# Sheet1.net
KiCad netlist of a schematic drawn in Altium Designer
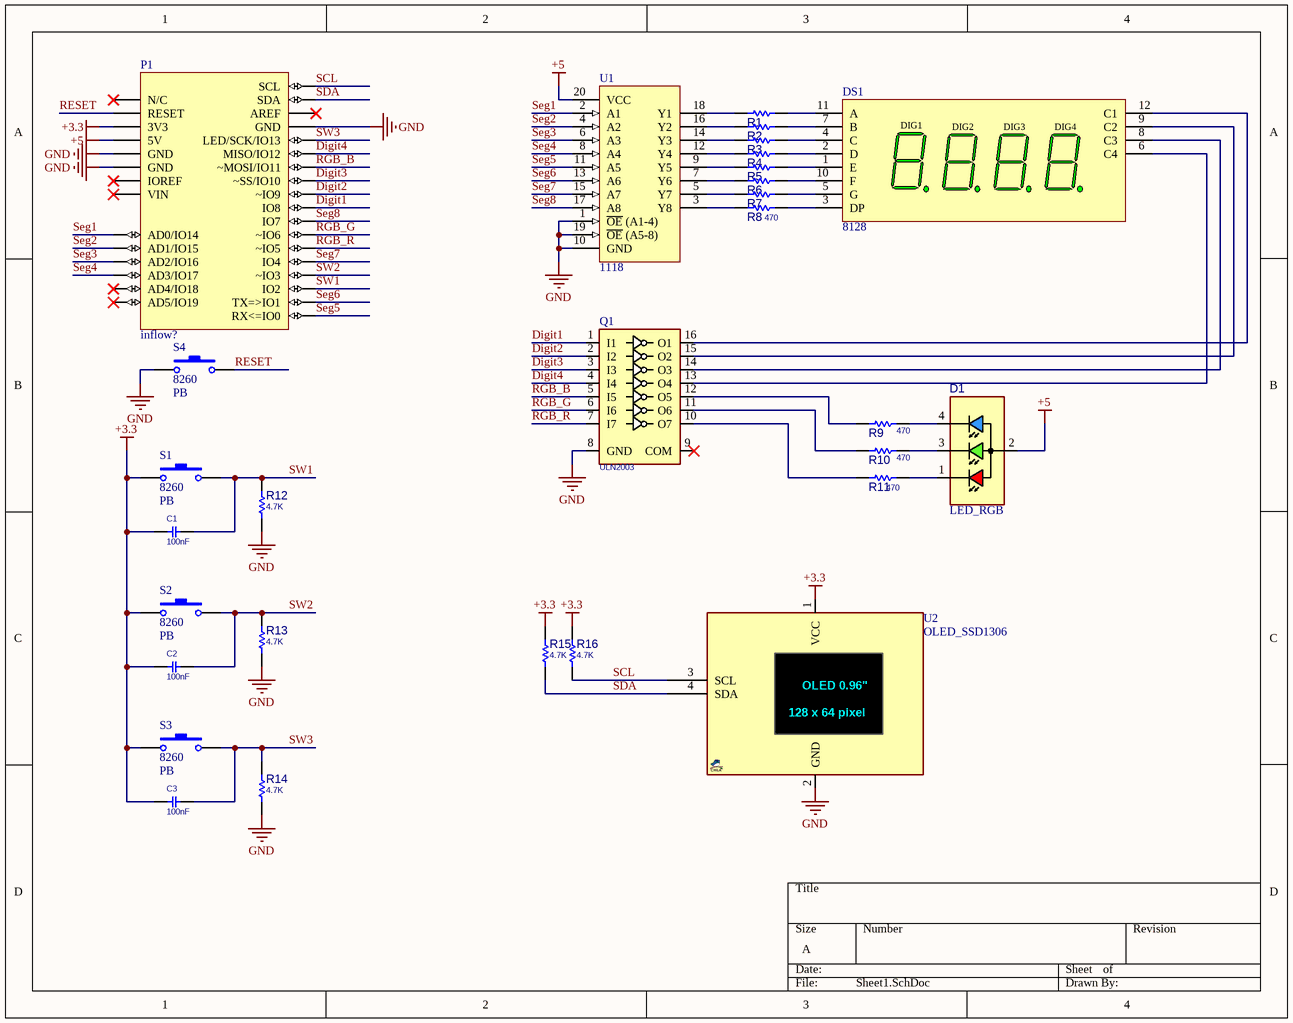
[diagram p0: Sheet1.SchDoc]

(export (version "E")
  (design (tool "Eeschema 10.0.6"))
  (components
    (comp (ref "C1")
      (value "100nF")
      (footprint "C_CER_D3")
      (description "CAP, THD, CER MULTI LAYER,")
      (fields (field (name "MANF_P#") "MANF_PART#") (field (name "MANF") "MANF"))
      (libsource (lib "Chila_PCB") (part "CAP_THD_CERML"))
    )
    (comp (ref "C2")
      (value "100nF")
      (footprint "C_CER_D3")
      (description "CAP, THD, CER MULTI LAYER,")
      (fields (field (name "MANF_P#") "MANF_PART#") (field (name "MANF") "MANF"))
      (libsource (lib "Chila_PCB") (part "CAP_THD_CERML"))
    )
    (comp (ref "C3")
      (value "100nF")
      (footprint "C_CER_D3")
      (description "CAP, THD, CER MULTI LAYER,")
      (fields (field (name "MANF_P#") "MANF_PART#") (field (name "MANF") "MANF"))
      (libsource (lib "Chila_PCB") (part "CAP_THD_CERML"))
    )
    (comp (ref "D1")
      (value "LED_RGB")
      (footprint "LED5RGB")
      (description "LED, THD, 5MM, RGB COMMON CATHODE")
      (fields (field (name "MANF_P#") "YSL-R596CR3G4B5C-C10") (field (name "MANF") "CHINA YOUNG"))
      (libsource (lib "Chila_PCB") (part "LED_THD_5MM_RGB_CA"))
    )
    (comp (ref "DS1")
      (value "4Digit, Red")
      (footprint "7Seg-MPX4-30.2x14.1mm")
      (description "7Segment-MPX4-CC")
      (fields (field (name "INFLOW") "8128"))
      (libsource (lib "aKaReZa") (part "ModSen_7Seg_MPX4_CC"))
    )
    (comp (ref "P1")
      (value "UNO")
      (footprint "Arduino_uno_S_3")
      (description "Arduino uno slave")
      (fields (field (name "INFLOW") "inflow?"))
      (libsource (lib "aKaReZa") (part "Con_Arduino_UNO_S"))
    )
    (comp (ref "Q1")
      (value "ULN2003")
      (footprint "DIP_16")
      (description "Darlington, 7-CH, 50V, 0.5A")
      (fields (field (name "MANF_P#") "ULN2003A") (field (name "MANF") "DIODES"))
      (libsource (lib "Chila_PCB") (part "ULN2003_DIP16"))
    )
    (comp (ref "R1")
      (value "470")
      (footprint "R1206")
      (description "RESISTOR, SMD")
      (libsource (lib "Chila_PCB") (part "RES_SMD_1206"))
    )
    (comp (ref "R2")
      (value "470")
      (footprint "R1206")
      (description "RESISTOR, SMD")
      (libsource (lib "Chila_PCB") (part "RES_SMD_1206"))
    )
    (comp (ref "R3")
      (value "470")
      (footprint "R1206")
      (description "RESISTOR, SMD")
      (libsource (lib "Chila_PCB") (part "RES_SMD_1206"))
    )
    (comp (ref "R4")
      (value "470")
      (footprint "R1206")
      (description "RESISTOR, SMD")
      (libsource (lib "Chila_PCB") (part "RES_SMD_1206"))
    )
    (comp (ref "R5")
      (value "470")
      (footprint "R1206")
      (description "RESISTOR, SMD")
      (libsource (lib "Chila_PCB") (part "RES_SMD_1206"))
    )
    (comp (ref "R6")
      (value "470")
      (footprint "R1206")
      (description "RESISTOR, SMD")
      (libsource (lib "Chila_PCB") (part "RES_SMD_1206"))
    )
    (comp (ref "R7")
      (value "470")
      (footprint "R1206")
      (description "RESISTOR, SMD")
      (libsource (lib "Chila_PCB") (part "RES_SMD_1206"))
    )
    (comp (ref "R8")
      (value "470")
      (footprint "R1206")
      (description "RESISTOR, SMD")
      (libsource (lib "Chila_PCB") (part "RES_SMD_1206"))
    )
    (comp (ref "R9")
      (value "470")
      (footprint "R1206")
      (description "RESISTOR, SMD")
      (libsource (lib "Chila_PCB") (part "RES_SMD_1206"))
    )
    (comp (ref "R10")
      (value "470")
      (footprint "R1206")
      (description "RESISTOR, SMD")
      (libsource (lib "Chila_PCB") (part "RES_SMD_1206"))
    )
    (comp (ref "R11")
      (value "470")
      (footprint "R1206")
      (description "RESISTOR, SMD")
      (libsource (lib "Chila_PCB") (part "RES_SMD_1206"))
    )
    (comp (ref "R12")
      (value "4.7K")
      (footprint "R1206")
      (description "RESISTOR, SMD")
      (libsource (lib "Chila_PCB") (part "RES_SMD_1206"))
    )
    (comp (ref "R13")
      (value "4.7K")
      (footprint "R1206")
      (description "RESISTOR, SMD")
      (libsource (lib "Chila_PCB") (part "RES_SMD_1206"))
    )
    (comp (ref "R14")
      (value "4.7K")
      (footprint "R1206")
      (description "RESISTOR, SMD")
      (libsource (lib "Chila_PCB") (part "RES_SMD_1206"))
    )
    (comp (ref "R15")
      (value "4.7K")
      (footprint "R1206")
      (description "RESISTOR, SMD")
      (libsource (lib "Chila_PCB") (part "RES_SMD_1206"))
    )
    (comp (ref "R16")
      (value "4.7K")
      (footprint "R1206")
      (description "RESISTOR, SMD")
      (libsource (lib "Chila_PCB") (part "RES_SMD_1206"))
    )
    (comp (ref "S1")
      (value "PB")
      (footprint "SW_PB_SMD_2PIN_SPST_6X3X2")
      (description "SMT Tactile ‎Switch")
      (fields (field (name "INFLOW") "8260"))
      (libsource (lib "aKaReZa") (part "SW_PushButton_2_SMD"))
    )
    (comp (ref "S2")
      (value "PB")
      (footprint "SW_PB_SMD_2PIN_SPST_6X3X2")
      (description "SMT Tactile ‎Switch")
      (fields (field (name "INFLOW") "8260"))
      (libsource (lib "aKaReZa") (part "SW_PushButton_2_SMD"))
    )
    (comp (ref "S3")
      (value "PB")
      (footprint "SW_PB_SMD_2PIN_SPST_6X3X2")
      (description "SMT Tactile ‎Switch")
      (fields (field (name "INFLOW") "8260"))
      (libsource (lib "aKaReZa") (part "SW_PushButton_2_SMD"))
    )
    (comp (ref "S4")
      (value "PB")
      (footprint "SW_PB_SMD_2PIN_SPST_6X3X2")
      (description "SMT Tactile ‎Switch")
      (fields (field (name "INFLOW") "8260"))
      (libsource (lib "aKaReZa") (part "SW_PushButton_2_SMD"))
    )
    (comp (ref "U1")
      (value "74HCT244")
      (footprint "PDIP20")
      (description "Octal Bus Buffer with 3 State Outputs (Non Inverted)")
      (fields (field (name "INFLOW") "1118"))
      (libsource (lib "aKaReZa") (part "IC_Logic_74HCT244"))
    )
    (comp (ref "U2")
      (value "OLED_SSD1306")
      (footprint "OLED_SSD1306_64_I2C")
      (description "OLED, SSD1306, 0.96\", 128X64, BREAKOUT I2C")
      (fields (field (name "MANF_P#") "OLED_SSD1306_I2C"))
      (libsource (lib "Chila_PCB") (part "OLED_SSD1306_64_I2C"))
    )
  )
  (nets
    (net (code "1") (name "+3.3") (class "Default")
      (node (ref "C1") (pin "1") (pinfunction "1_1") (pintype "passive"))
      (node (ref "C2") (pin "1") (pinfunction "1_1") (pintype "passive"))
      (node (ref "C3") (pin "1") (pinfunction "1_1") (pintype "passive"))
      (node (ref "P1") (pin "4") (pinfunction "3V3_4") (pintype "power_in"))
      (node (ref "R15") (pin "2") (pinfunction "2_2") (pintype "passive"))
      (node (ref "R16") (pin "2") (pinfunction "2_2") (pintype "passive"))
      (node (ref "S1") (pin "1") (pinfunction "1_1") (pintype "passive"))
      (node (ref "S2") (pin "1") (pinfunction "1_1") (pintype "passive"))
      (node (ref "S3") (pin "1") (pinfunction "1_1") (pintype "passive"))
      (node (ref "U2") (pin "1") (pinfunction "VCC_1") (pintype "passive"))
    )
    (net (code "2") (name "+5") (class "Default")
      (node (ref "D1") (pin "2") (pinfunction "C_2") (pintype "passive"))
      (node (ref "P1") (pin "5") (pinfunction "5V_5") (pintype "power_in"))
      (node (ref "U1") (pin "20") (pinfunction "VCC_20") (pintype "power_in"))
    )
    (net (code "3") (name "/Digit1") (class "Default")
      (node (ref "P1") (pin "23") (pinfunction "IO8_23") (pintype "bidirectional"))
      (node (ref "Q1") (pin "1") (pinfunction "I1_1") (pintype "passive"))
    )
    (net (code "4") (name "/Digit2") (class "Default")
      (node (ref "P1") (pin "24") (pinfunction "~IO9_24") (pintype "bidirectional"))
      (node (ref "Q1") (pin "2") (pinfunction "I2_2") (pintype "passive"))
    )
    (net (code "5") (name "/Digit3") (class "Default")
      (node (ref "P1") (pin "25") (pinfunction "~SS/IO10_25") (pintype "bidirectional"))
      (node (ref "Q1") (pin "3") (pinfunction "I3_3") (pintype "passive"))
    )
    (net (code "6") (name "/Digit4") (class "Default")
      (node (ref "P1") (pin "27") (pinfunction "MISO/IO12_27") (pintype "bidirectional"))
      (node (ref "Q1") (pin "4") (pinfunction "I4_4") (pintype "passive"))
    )
    (net (code "7") (name "/RESET") (class "Default")
      (node (ref "P1") (pin "3") (pinfunction "RESET_3") (pintype "passive"))
      (node (ref "S4") (pin "2") (pinfunction "2_2") (pintype "passive"))
    )
    (net (code "8") (name "/RGB_B") (class "Default")
      (node (ref "P1") (pin "26") (pinfunction "~MOSI/IO11_26") (pintype "bidirectional"))
      (node (ref "Q1") (pin "5") (pinfunction "I5_5") (pintype "passive"))
    )
    (net (code "9") (name "/RGB_G") (class "Default")
      (node (ref "P1") (pin "21") (pinfunction "~IO6_21") (pintype "bidirectional"))
      (node (ref "Q1") (pin "6") (pinfunction "I6_6") (pintype "passive"))
    )
    (net (code "10") (name "/RGB_R") (class "Default")
      (node (ref "P1") (pin "20") (pinfunction "~IO5_20") (pintype "bidirectional"))
      (node (ref "Q1") (pin "7") (pinfunction "I7_7") (pintype "passive"))
    )
    (net (code "11") (name "/SCL") (class "Default")
      (node (ref "P1") (pin "32") (pinfunction "SCL_32") (pintype "bidirectional"))
      (node (ref "R16") (pin "1") (pinfunction "1_1") (pintype "passive"))
      (node (ref "U2") (pin "3") (pinfunction "SCL_3") (pintype "passive"))
    )
    (net (code "12") (name "/SDA") (class "Default")
      (node (ref "P1") (pin "31") (pinfunction "SDA_31") (pintype "bidirectional"))
      (node (ref "R15") (pin "1") (pinfunction "1_1") (pintype "passive"))
      (node (ref "U2") (pin "4") (pinfunction "SDA_4") (pintype "passive"))
    )
    (net (code "13") (name "/SW1") (class "Default")
      (node (ref "C1") (pin "2") (pinfunction "2_2") (pintype "passive"))
      (node (ref "P1") (pin "17") (pinfunction "IO2_17") (pintype "bidirectional"))
      (node (ref "R12") (pin "2") (pinfunction "2_2") (pintype "passive"))
      (node (ref "S1") (pin "2") (pinfunction "2_2") (pintype "passive"))
    )
    (net (code "14") (name "/SW2") (class "Default")
      (node (ref "C2") (pin "2") (pinfunction "2_2") (pintype "passive"))
      (node (ref "P1") (pin "18") (pinfunction "~IO3_18") (pintype "bidirectional"))
      (node (ref "R13") (pin "2") (pinfunction "2_2") (pintype "passive"))
      (node (ref "S2") (pin "2") (pinfunction "2_2") (pintype "passive"))
    )
    (net (code "15") (name "/SW3") (class "Default")
      (node (ref "C3") (pin "2") (pinfunction "2_2") (pintype "passive"))
      (node (ref "P1") (pin "28") (pinfunction "LED/SCK/IO13_28") (pintype "bidirectional"))
      (node (ref "R14") (pin "2") (pinfunction "2_2") (pintype "passive"))
      (node (ref "S3") (pin "2") (pinfunction "2_2") (pintype "passive"))
    )
    (net (code "16") (name "/Seg1") (class "Default")
      (node (ref "P1") (pin "9") (pinfunction "AD0/IO14_9") (pintype "bidirectional"))
      (node (ref "U1") (pin "2") (pinfunction "A1_2") (pintype "input"))
    )
    (net (code "17") (name "/Seg2") (class "Default")
      (node (ref "P1") (pin "10") (pinfunction "AD1/IO15_10") (pintype "bidirectional"))
      (node (ref "U1") (pin "4") (pinfunction "A2_4") (pintype "input"))
    )
    (net (code "18") (name "/Seg3") (class "Default")
      (node (ref "P1") (pin "11") (pinfunction "AD2/IO16_11") (pintype "bidirectional"))
      (node (ref "U1") (pin "6") (pinfunction "A3_6") (pintype "input"))
    )
    (net (code "19") (name "/Seg4") (class "Default")
      (node (ref "P1") (pin "12") (pinfunction "AD3/IO17_12") (pintype "bidirectional"))
      (node (ref "U1") (pin "8") (pinfunction "A4_8") (pintype "input"))
    )
    (net (code "20") (name "/Seg5") (class "Default")
      (node (ref "P1") (pin "15") (pinfunction "RX<=IO0_15") (pintype "bidirectional"))
      (node (ref "U1") (pin "11") (pinfunction "A5_11") (pintype "input"))
    )
    (net (code "21") (name "/Seg6") (class "Default")
      (node (ref "P1") (pin "16") (pinfunction "TX=>IO1_16") (pintype "bidirectional"))
      (node (ref "U1") (pin "13") (pinfunction "A6_13") (pintype "input"))
    )
    (net (code "22") (name "/Seg7") (class "Default")
      (node (ref "P1") (pin "19") (pinfunction "IO4_19") (pintype "bidirectional"))
      (node (ref "U1") (pin "15") (pinfunction "A7_15") (pintype "input"))
    )
    (net (code "23") (name "/Seg8") (class "Default")
      (node (ref "P1") (pin "22") (pinfunction "IO7_22") (pintype "bidirectional"))
      (node (ref "U1") (pin "17") (pinfunction "A8_17") (pintype "input"))
    )
    (net (code "24") (name "GND") (class "Default")
      (node (ref "P1") (pin "29") (pinfunction "GND_29") (pintype "power_in"))
      (node (ref "P1") (pin "6") (pinfunction "GND_6") (pintype "power_in"))
      (node (ref "P1") (pin "7") (pinfunction "GND_7") (pintype "power_in"))
      (node (ref "Q1") (pin "8") (pinfunction "GND_8") (pintype "passive"))
      (node (ref "R12") (pin "1") (pinfunction "1_1") (pintype "passive"))
      (node (ref "R13") (pin "1") (pinfunction "1_1") (pintype "passive"))
      (node (ref "R14") (pin "1") (pinfunction "1_1") (pintype "passive"))
      (node (ref "S4") (pin "1") (pinfunction "1_1") (pintype "passive"))
      (node (ref "U1") (pin "1") (pinfunction "~{OE}_(A1-4)_1") (pintype "input"))
      (node (ref "U1") (pin "10") (pinfunction "GND_10") (pintype "power_in"))
      (node (ref "U1") (pin "19") (pinfunction "~{OE}_(A5-8)_19") (pintype "input"))
      (node (ref "U2") (pin "2") (pinfunction "GND_2") (pintype "passive"))
    )
    (net (code "25") (name "Net-(D1-BLU)") (class "Default")
      (node (ref "D1") (pin "4") (pinfunction "BLU_4") (pintype "passive"))
      (node (ref "R9") (pin "2") (pinfunction "2_2") (pintype "passive"))
    )
    (net (code "26") (name "Net-(D1-GRN)") (class "Default")
      (node (ref "D1") (pin "3") (pinfunction "GRN_3") (pintype "passive"))
      (node (ref "R10") (pin "2") (pinfunction "2_2") (pintype "passive"))
    )
    (net (code "27") (name "Net-(D1-RED)") (class "Default")
      (node (ref "D1") (pin "1") (pinfunction "RED_1") (pintype "passive"))
      (node (ref "R11") (pin "2") (pinfunction "2_2") (pintype "passive"))
    )
    (net (code "28") (name "Net-(DS1-A)") (class "Default")
      (node (ref "DS1") (pin "11") (pinfunction "A_11") (pintype "passive"))
      (node (ref "R1") (pin "2") (pinfunction "2_2") (pintype "passive"))
    )
    (net (code "29") (name "Net-(DS1-B)") (class "Default")
      (node (ref "DS1") (pin "7") (pinfunction "B_7") (pintype "passive"))
      (node (ref "R2") (pin "2") (pinfunction "2_2") (pintype "passive"))
    )
    (net (code "30") (name "Net-(DS1-C)") (class "Default")
      (node (ref "DS1") (pin "4") (pinfunction "C_4") (pintype "passive"))
      (node (ref "R3") (pin "2") (pinfunction "2_2") (pintype "passive"))
    )
    (net (code "31") (name "Net-(DS1-C1)") (class "Default")
      (node (ref "DS1") (pin "12") (pinfunction "C1_12") (pintype "passive"))
      (node (ref "Q1") (pin "16") (pinfunction "O1_16") (pintype "passive"))
    )
    (net (code "32") (name "Net-(DS1-C2)") (class "Default")
      (node (ref "DS1") (pin "9") (pinfunction "C2_9") (pintype "passive"))
      (node (ref "Q1") (pin "15") (pinfunction "O2_15") (pintype "passive"))
    )
    (net (code "33") (name "Net-(DS1-C3)") (class "Default")
      (node (ref "DS1") (pin "8") (pinfunction "C3_8") (pintype "passive"))
      (node (ref "Q1") (pin "14") (pinfunction "O3_14") (pintype "passive"))
    )
    (net (code "34") (name "Net-(DS1-C4)") (class "Default")
      (node (ref "DS1") (pin "6") (pinfunction "C4_6") (pintype "passive"))
      (node (ref "Q1") (pin "13") (pinfunction "O4_13") (pintype "passive"))
    )
    (net (code "35") (name "Net-(DS1-D)") (class "Default")
      (node (ref "DS1") (pin "2") (pinfunction "D_2") (pintype "passive"))
      (node (ref "R4") (pin "2") (pinfunction "2_2") (pintype "passive"))
    )
    (net (code "36") (name "Net-(DS1-DP)") (class "Default")
      (node (ref "DS1") (pin "3") (pinfunction "DP_3") (pintype "passive"))
      (node (ref "R8") (pin "2") (pinfunction "2_2") (pintype "passive"))
    )
    (net (code "37") (name "Net-(DS1-E)") (class "Default")
      (node (ref "DS1") (pin "1") (pinfunction "E_1") (pintype "passive"))
      (node (ref "R5") (pin "2") (pinfunction "2_2") (pintype "passive"))
    )
    (net (code "38") (name "Net-(DS1-F)") (class "Default")
      (node (ref "DS1") (pin "10") (pinfunction "F_10") (pintype "passive"))
      (node (ref "R6") (pin "2") (pinfunction "2_2") (pintype "passive"))
    )
    (net (code "39") (name "Net-(DS1-G)") (class "Default")
      (node (ref "DS1") (pin "5") (pinfunction "G_5") (pintype "passive"))
      (node (ref "R7") (pin "2") (pinfunction "2_2") (pintype "passive"))
    )
    (net (code "40") (name "Net-(Q1-O5)") (class "Default")
      (node (ref "Q1") (pin "12") (pinfunction "O5_12") (pintype "passive"))
      (node (ref "R9") (pin "1") (pinfunction "1_1") (pintype "passive"))
    )
    (net (code "41") (name "Net-(Q1-O6)") (class "Default")
      (node (ref "Q1") (pin "11") (pinfunction "O6_11") (pintype "passive"))
      (node (ref "R10") (pin "1") (pinfunction "1_1") (pintype "passive"))
    )
    (net (code "42") (name "Net-(Q1-O7)") (class "Default")
      (node (ref "Q1") (pin "10") (pinfunction "O7_10") (pintype "passive"))
      (node (ref "R11") (pin "1") (pinfunction "1_1") (pintype "passive"))
    )
    (net (code "43") (name "Net-(U1-Y1)") (class "Default")
      (node (ref "R1") (pin "1") (pinfunction "1_1") (pintype "passive"))
      (node (ref "U1") (pin "18") (pinfunction "Y1_18") (pintype "tri_state"))
    )
    (net (code "44") (name "Net-(U1-Y2)") (class "Default")
      (node (ref "R2") (pin "1") (pinfunction "1_1") (pintype "passive"))
      (node (ref "U1") (pin "16") (pinfunction "Y2_16") (pintype "tri_state"))
    )
    (net (code "45") (name "Net-(U1-Y3)") (class "Default")
      (node (ref "R3") (pin "1") (pinfunction "1_1") (pintype "passive"))
      (node (ref "U1") (pin "14") (pinfunction "Y3_14") (pintype "tri_state"))
    )
    (net (code "46") (name "Net-(U1-Y4)") (class "Default")
      (node (ref "R4") (pin "1") (pinfunction "1_1") (pintype "passive"))
      (node (ref "U1") (pin "12") (pinfunction "Y4_12") (pintype "tri_state"))
    )
    (net (code "47") (name "Net-(U1-Y5)") (class "Default")
      (node (ref "R5") (pin "1") (pinfunction "1_1") (pintype "passive"))
      (node (ref "U1") (pin "9") (pinfunction "Y5_9") (pintype "tri_state"))
    )
    (net (code "48") (name "Net-(U1-Y6)") (class "Default")
      (node (ref "R6") (pin "1") (pinfunction "1_1") (pintype "passive"))
      (node (ref "U1") (pin "7") (pinfunction "Y6_7") (pintype "tri_state"))
    )
    (net (code "49") (name "Net-(U1-Y7)") (class "Default")
      (node (ref "R7") (pin "1") (pinfunction "1_1") (pintype "passive"))
      (node (ref "U1") (pin "5") (pinfunction "Y7_5") (pintype "tri_state"))
    )
    (net (code "50") (name "Net-(U1-Y8)") (class "Default")
      (node (ref "R8") (pin "1") (pinfunction "1_1") (pintype "passive"))
      (node (ref "U1") (pin "3") (pinfunction "Y8_3") (pintype "tri_state"))
    )
    (net (code "51") (name "unconnected-(P1-AD4{slash}IO18-Pad13)") (class "Default")
      (node (ref "P1") (pin "13") (pinfunction "AD4/IO18_13") (pintype "bidirectional+no_connect"))
    )
    (net (code "52") (name "unconnected-(P1-AD5{slash}IO19-Pad14)") (class "Default")
      (node (ref "P1") (pin "14") (pinfunction "AD5/IO19_14") (pintype "bidirectional+no_connect"))
    )
    (net (code "53") (name "unconnected-(P1-AREF-Pad30)") (class "Default")
      (node (ref "P1") (pin "30") (pinfunction "AREF_30") (pintype "passive+no_connect"))
    )
    (net (code "54") (name "unconnected-(P1-IOREF-Pad2)") (class "Default")
      (node (ref "P1") (pin "2") (pinfunction "IOREF_2") (pintype "power_in+no_connect"))
    )
    (net (code "55") (name "unconnected-(P1-N{slash}C-Pad1)") (class "Default")
      (node (ref "P1") (pin "1") (pinfunction "N/C_1") (pintype "passive+no_connect"))
    )
    (net (code "56") (name "unconnected-(P1-VIN-Pad8)") (class "Default")
      (node (ref "P1") (pin "8") (pinfunction "VIN_8") (pintype "power_in+no_connect"))
    )
    (net (code "57") (name "unconnected-(Q1-COM-Pad9)") (class "Default")
      (node (ref "Q1") (pin "9") (pinfunction "COM_9") (pintype "passive+no_connect"))
    )
  )
)
